# 2__FPGA.net
KiCad netlist of a schematic drawn in Altium Designer
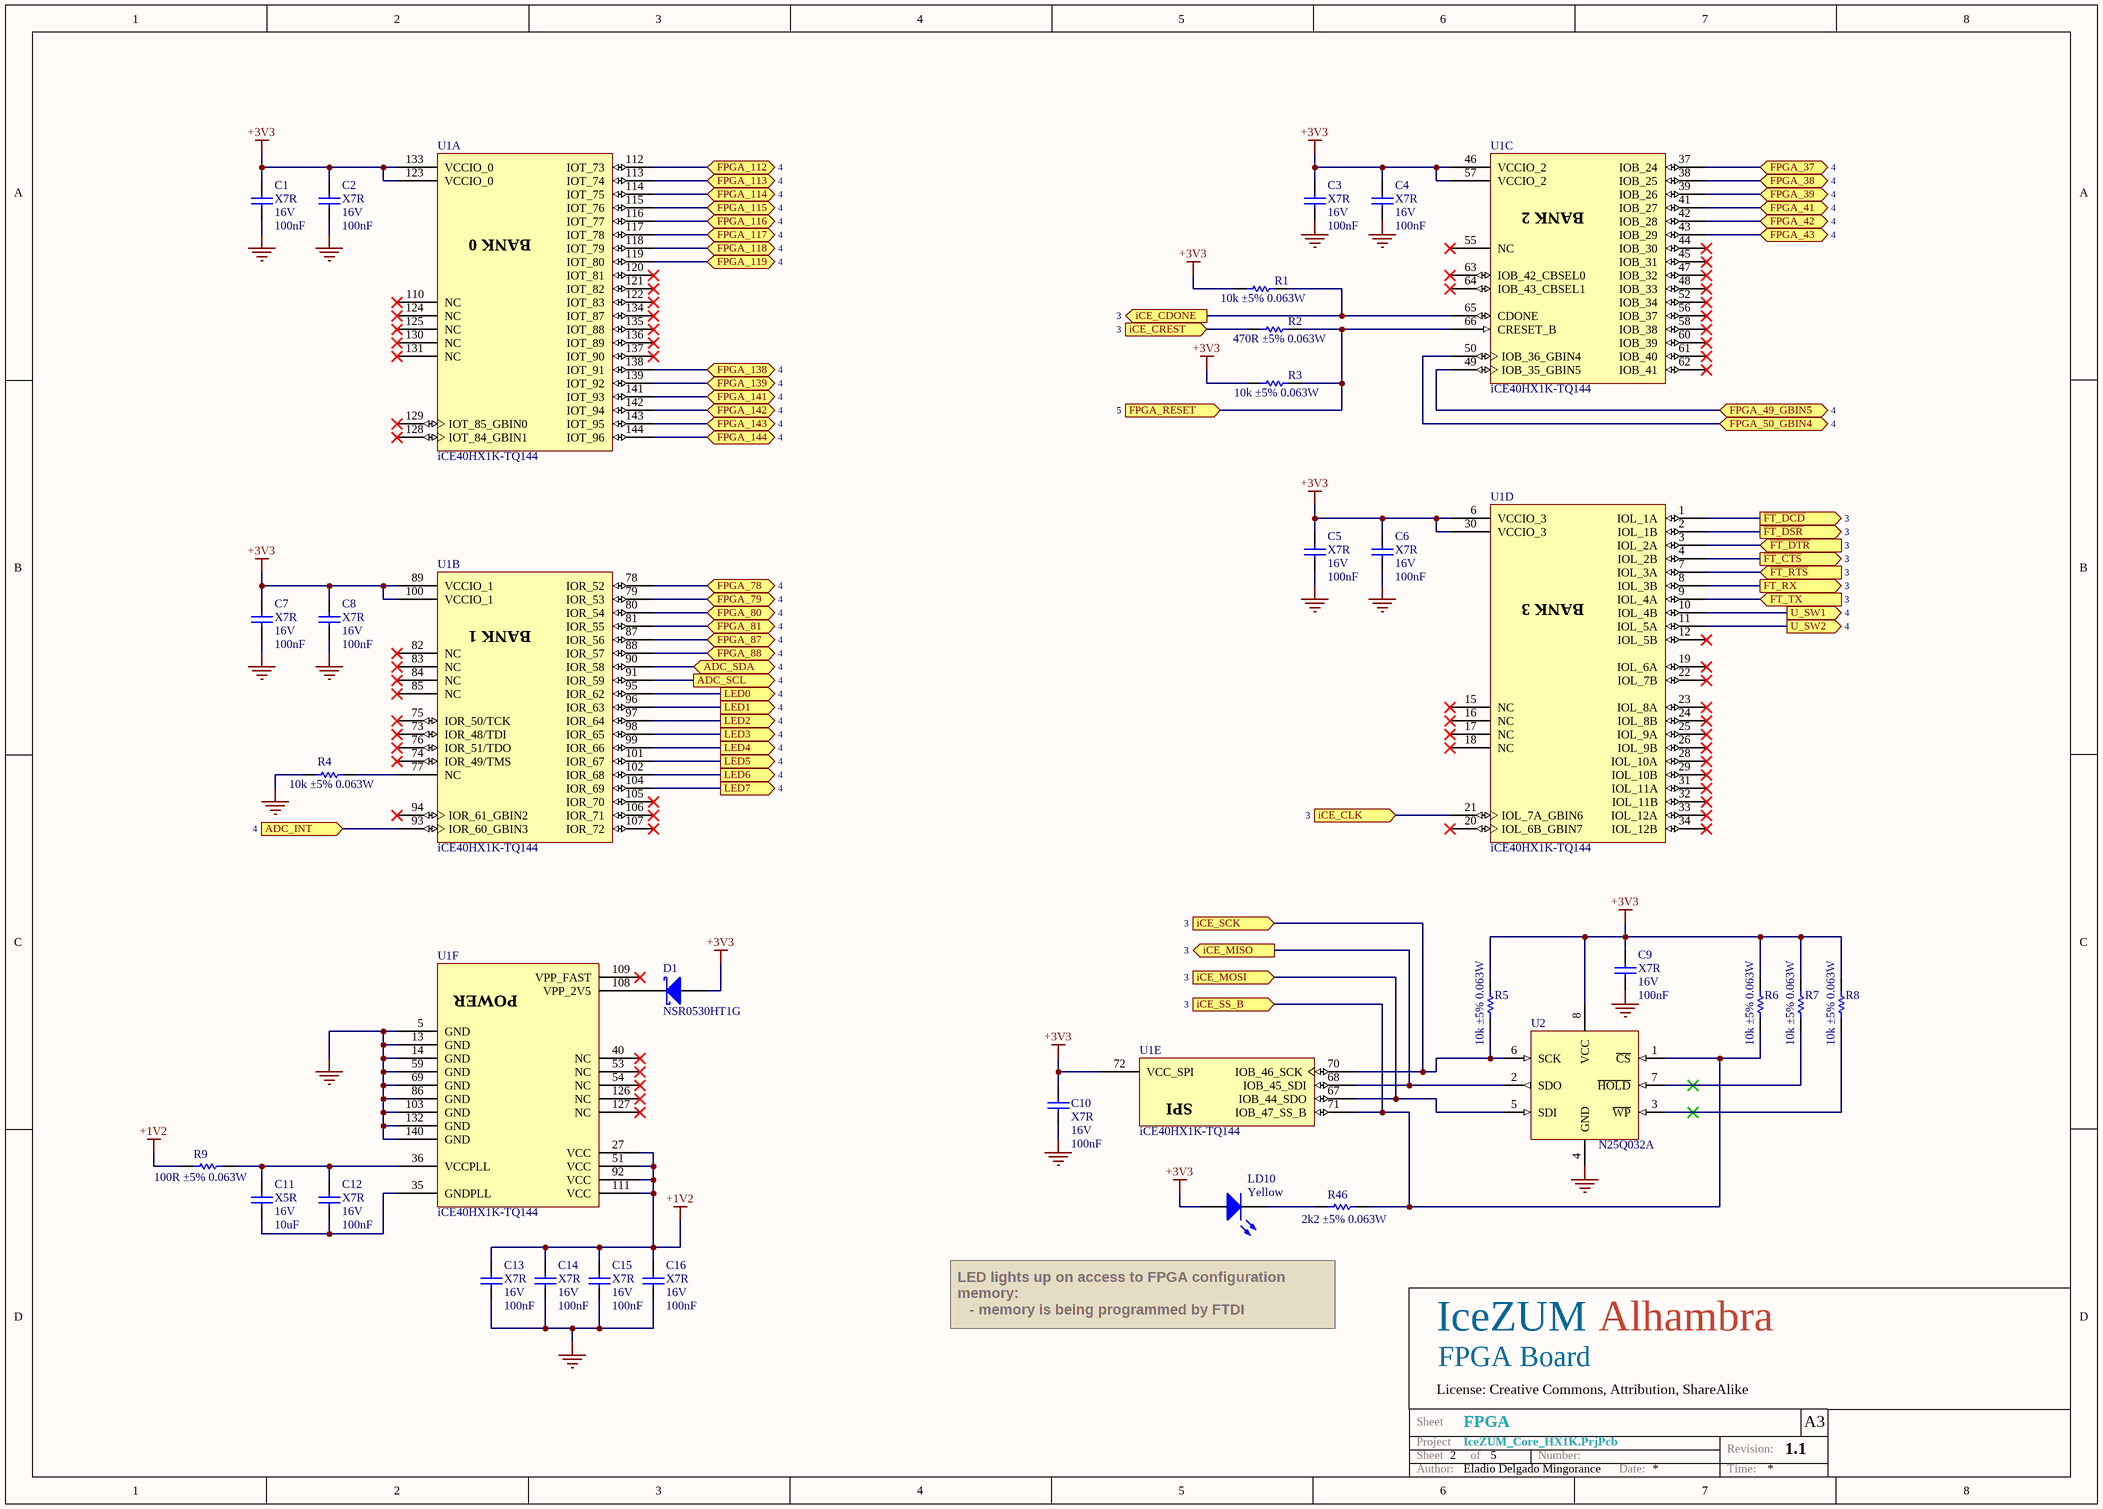
[diagram p0: [2]_FPGA.SchDoc]

(export (version "E")
  (design (tool "Eeschema 10.0.6"))
  (components
    (comp (ref "C1")
      (value "Capacitor")
      (footprint "C0402:C0402")
      (description "Capacitor SMD")
      (fields
        (field (name "DIELECTRIC") "X7R")
        (field (name "VOLTAGE") "16V")
        (field (name "CAPACITANCE") "100nF")
        (field (name "PART NUMBER") "C0402_100nF_16V_±10%")
        (field (name "TOLERANCE") "±10%")
      )
      (libsource (lib "Pasives_Capacitor_SMD") (part "Capacitor"))
    )
    (comp (ref "C2")
      (value "Capacitor")
      (footprint "C0402:C0402")
      (description "Capacitor SMD")
      (fields
        (field (name "DIELECTRIC") "X7R")
        (field (name "VOLTAGE") "16V")
        (field (name "CAPACITANCE") "100nF")
        (field (name "PART NUMBER") "C0402_100nF_16V_±10%")
        (field (name "TOLERANCE") "±10%")
      )
      (libsource (lib "Pasives_Capacitor_SMD") (part "Capacitor"))
    )
    (comp (ref "C3")
      (value "Capacitor")
      (footprint "C0402")
      (description "Capacitor SMD")
      (fields
        (field (name "DIELECTRIC") "X7R")
        (field (name "VOLTAGE") "16V")
        (field (name "CAPACITANCE") "100nF")
        (field (name "PART NUMBER") "C0402_100nF_16V_±10%")
        (field (name "TOLERANCE") "±10%")
      )
      (libsource (lib "Pasives_Capacitor_SMD") (part "Capacitor"))
    )
    (comp (ref "C4")
      (value "Capacitor")
      (footprint "C0402")
      (description "Capacitor SMD")
      (fields
        (field (name "DIELECTRIC") "X7R")
        (field (name "VOLTAGE") "16V")
        (field (name "CAPACITANCE") "100nF")
        (field (name "PART NUMBER") "C0402_100nF_16V_±10%")
        (field (name "TOLERANCE") "±10%")
      )
      (libsource (lib "Pasives_Capacitor_SMD") (part "Capacitor"))
    )
    (comp (ref "C5")
      (value "Capacitor")
      (footprint "C0402")
      (description "Capacitor SMD")
      (fields
        (field (name "DIELECTRIC") "X7R")
        (field (name "VOLTAGE") "16V")
        (field (name "CAPACITANCE") "100nF")
        (field (name "PART NUMBER") "C0402_100nF_16V_±10%")
        (field (name "TOLERANCE") "±10%")
      )
      (libsource (lib "Pasives_Capacitor_SMD") (part "Capacitor"))
    )
    (comp (ref "C6")
      (value "Capacitor")
      (footprint "C0402")
      (description "Capacitor SMD")
      (fields
        (field (name "DIELECTRIC") "X7R")
        (field (name "VOLTAGE") "16V")
        (field (name "CAPACITANCE") "100nF")
        (field (name "PART NUMBER") "C0402_100nF_16V_±10%")
        (field (name "TOLERANCE") "±10%")
      )
      (libsource (lib "Pasives_Capacitor_SMD") (part "Capacitor"))
    )
    (comp (ref "C7")
      (value "Capacitor")
      (footprint "C0402")
      (description "Capacitor SMD")
      (fields
        (field (name "DIELECTRIC") "X7R")
        (field (name "VOLTAGE") "16V")
        (field (name "CAPACITANCE") "100nF")
        (field (name "PART NUMBER") "C0402_100nF_16V_±10%")
        (field (name "TOLERANCE") "±10%")
      )
      (libsource (lib "Pasives_Capacitor_SMD") (part "Capacitor"))
    )
    (comp (ref "C8")
      (value "Capacitor")
      (footprint "C0402")
      (description "Capacitor SMD")
      (fields
        (field (name "DIELECTRIC") "X7R")
        (field (name "VOLTAGE") "16V")
        (field (name "CAPACITANCE") "100nF")
        (field (name "PART NUMBER") "C0402_100nF_16V_±10%")
        (field (name "TOLERANCE") "±10%")
      )
      (libsource (lib "Pasives_Capacitor_SMD") (part "Capacitor"))
    )
    (comp (ref "C9")
      (value "Capacitor")
      (footprint "C0402")
      (description "Capacitor SMD")
      (fields
        (field (name "DIELECTRIC") "X7R")
        (field (name "VOLTAGE") "16V")
        (field (name "CAPACITANCE") "100nF")
        (field (name "PART NUMBER") "C0402_100nF_16V_±10%")
        (field (name "TOLERANCE") "±10%")
      )
      (libsource (lib "Pasives_Capacitor_SMD") (part "Capacitor"))
    )
    (comp (ref "C10")
      (value "Capacitor")
      (footprint "C0402")
      (description "Capacitor SMD")
      (fields
        (field (name "DIELECTRIC") "X7R")
        (field (name "VOLTAGE") "16V")
        (field (name "CAPACITANCE") "100nF")
        (field (name "PART NUMBER") "C0402_100nF_16V_±10%")
        (field (name "TOLERANCE") "±10%")
      )
      (libsource (lib "Pasives_Capacitor_SMD") (part "Capacitor"))
    )
    (comp (ref "C11")
      (value "Capacitor")
      (footprint "C0603")
      (description "Capacitor SMD")
      (fields
        (field (name "DIELECTRIC") "X5R")
        (field (name "VOLTAGE") "16V")
        (field (name "CAPACITANCE") "10uF")
        (field (name "PART NUMBER") "C0603_10uF_16V_±20%")
        (field (name "TOLERANCE") "±20%")
      )
      (libsource (lib "Pasives_Capacitor_SMD") (part "Capacitor"))
    )
    (comp (ref "C12")
      (value "Capacitor")
      (footprint "C0402")
      (description "Capacitor SMD")
      (fields
        (field (name "DIELECTRIC") "X7R")
        (field (name "VOLTAGE") "16V")
        (field (name "CAPACITANCE") "100nF")
        (field (name "PART NUMBER") "C0402_100nF_16V_±10%")
        (field (name "TOLERANCE") "±10%")
      )
      (libsource (lib "Pasives_Capacitor_SMD") (part "Capacitor"))
    )
    (comp (ref "C13")
      (value "Capacitor")
      (footprint "C0402")
      (description "Capacitor SMD")
      (fields
        (field (name "DIELECTRIC") "X7R")
        (field (name "VOLTAGE") "16V")
        (field (name "CAPACITANCE") "100nF")
        (field (name "PART NUMBER") "C0402_100nF_16V_±10%")
        (field (name "TOLERANCE") "±10%")
      )
      (libsource (lib "Pasives_Capacitor_SMD") (part "Capacitor"))
    )
    (comp (ref "C14")
      (value "Capacitor")
      (footprint "C0402")
      (description "Capacitor SMD")
      (fields
        (field (name "DIELECTRIC") "X7R")
        (field (name "VOLTAGE") "16V")
        (field (name "CAPACITANCE") "100nF")
        (field (name "PART NUMBER") "C0402_100nF_16V_±10%")
        (field (name "TOLERANCE") "±10%")
      )
      (libsource (lib "Pasives_Capacitor_SMD") (part "Capacitor"))
    )
    (comp (ref "C15")
      (value "Capacitor")
      (footprint "C0402")
      (description "Capacitor SMD")
      (fields
        (field (name "DIELECTRIC") "X7R")
        (field (name "VOLTAGE") "16V")
        (field (name "CAPACITANCE") "100nF")
        (field (name "PART NUMBER") "C0402_100nF_16V_±10%")
        (field (name "TOLERANCE") "±10%")
      )
      (libsource (lib "Pasives_Capacitor_SMD") (part "Capacitor"))
    )
    (comp (ref "C16")
      (value "Capacitor")
      (footprint "C0402")
      (description "Capacitor SMD")
      (fields
        (field (name "DIELECTRIC") "X7R")
        (field (name "VOLTAGE") "16V")
        (field (name "CAPACITANCE") "100nF")
        (field (name "PART NUMBER") "C0402_100nF_16V_±10%")
        (field (name "TOLERANCE") "±10%")
      )
      (libsource (lib "Pasives_Capacitor_SMD") (part "Capacitor"))
    )
    (comp (ref "D1")
      (value "NSR0530HT1G")
      (footprint "SOD323")
      (description "Schottky Diode")
      (fields (field (name "MANUFACTURER") "On Semiconductor"))
      (libsource (lib "Diodes") (part "Schottky"))
    )
    (comp (ref "LD10")
      (value "Yellow")
      (footprint "LED0603")
      (description "LED")
      (fields (field (name "PART NUMBER") "LED Yellow 0603") (field (name "MANUFACTURER") "KINGBRIGHT"))
      (libsource (lib "Optoelectronics") (part "LED"))
    )
    (comp (ref "R1")
      (value "10k ±5% 0.063W")
      (footprint "R0402")
      (description "Resistor, SMD")
      (fields (field (name "TOLERANCE") "±5%") (field (name "POWER") "0.063W"))
      (libsource (lib "Pasives_Resistor_SMD") (part "Resistor"))
    )
    (comp (ref "R2")
      (value "470R ±5% 0.063W")
      (footprint "R0402")
      (description "Resistor, SMD")
      (fields (field (name "TOLERANCE") "±5%") (field (name "POWER") "0.063W"))
      (libsource (lib "Pasives_Resistor_SMD") (part "Resistor"))
    )
    (comp (ref "R3")
      (value "10k ±5% 0.063W")
      (footprint "R0402")
      (description "Resistor, SMD")
      (fields (field (name "TOLERANCE") "±5%") (field (name "POWER") "0.063W"))
      (libsource (lib "Pasives_Resistor_SMD") (part "Resistor"))
    )
    (comp (ref "R4")
      (value "10k ±5% 0.063W")
      (footprint "R0402")
      (description "Resistor, SMD")
      (fields (field (name "TOLERANCE") "±5%") (field (name "POWER") "0.063W"))
      (libsource (lib "Pasives_Resistor_SMD") (part "Resistor"))
    )
    (comp (ref "R5")
      (value "10k ±5% 0.063W")
      (footprint "R0402")
      (description "Resistor, SMD")
      (fields (field (name "TOLERANCE") "±5%") (field (name "POWER") "0.063W"))
      (libsource (lib "Pasives_Resistor_SMD") (part "Resistor"))
    )
    (comp (ref "R6")
      (value "10k ±5% 0.063W")
      (footprint "R0402")
      (description "Resistor, SMD")
      (fields (field (name "TOLERANCE") "±5%") (field (name "POWER") "0.063W"))
      (libsource (lib "Pasives_Resistor_SMD") (part "Resistor"))
    )
    (comp (ref "R7")
      (value "10k ±5% 0.063W")
      (footprint "R0402")
      (description "Resistor, SMD")
      (fields (field (name "TOLERANCE") "±5%") (field (name "POWER") "0.063W"))
      (libsource (lib "Pasives_Resistor_SMD") (part "Resistor"))
    )
    (comp (ref "R8")
      (value "10k ±5% 0.063W")
      (footprint "R0402")
      (description "Resistor, SMD")
      (fields (field (name "TOLERANCE") "±5%") (field (name "POWER") "0.063W"))
      (libsource (lib "Pasives_Resistor_SMD") (part "Resistor"))
    )
    (comp (ref "R9")
      (value "100R ±5% 0.063W")
      (footprint "R0402")
      (description "Resistor, SMD")
      (fields (field (name "TOLERANCE") "±5%") (field (name "POWER") "0.063W"))
      (libsource (lib "Pasives_Resistor_SMD") (part "Resistor"))
    )
    (comp (ref "R46")
      (value "2k2 ±5% 0.063W")
      (footprint "R0402")
      (description "Resistor, SMD")
      (fields (field (name "TOLERANCE") "±5%") (field (name "POWER") "0.063W"))
      (libsource (lib "Pasives_Resistor_SMD") (part "Resistor"))
    )
    (comp (ref "U1")
      (value "iCE40HX1K-TQ144")
      (footprint "TQFP-144_IPC-MD_HX1K")
      (fields (field (name "PART NUMBER") "iCE40-HX1K") (field (name "MANUFACTURER") "Lattice"))
      (libsource (lib "FPGA") (part "iCE40HX1K-TQ144"))
    )
    (comp (ref "U2")
      (value "N25Q032A")
      (footprint "DFN-8 6x5mm")
      (description "NOR Flash Memory, serial")
      (fields (field (name "MANUFACTURER") "Micron"))
      (libsource (lib "Memory_Serial") (part "N25Q032A"))
    )
  )
  (nets
    (net (code "1") (name "+1V2") (class "Default")
      (node (ref "C13") (pin "2") (pinfunction "2_2") (pintype "passive"))
      (node (ref "C14") (pin "2") (pinfunction "2_2") (pintype "passive"))
      (node (ref "C15") (pin "2") (pinfunction "2_2") (pintype "passive"))
      (node (ref "C16") (pin "2") (pinfunction "2_2") (pintype "passive"))
      (node (ref "R9") (pin "2") (pinfunction "2_2") (pintype "passive"))
      (node (ref "U1") (pin "111") (pinfunction "VCC_111") (pintype "power_in"))
      (node (ref "U1") (pin "27") (pinfunction "VCC_27") (pintype "power_in"))
      (node (ref "U1") (pin "51") (pinfunction "VCC_51") (pintype "power_in"))
      (node (ref "U1") (pin "92") (pinfunction "VCC_92") (pintype "power_in"))
    )
    (net (code "2") (name "+3V3") (class "Default")
      (node (ref "C1") (pin "2") (pinfunction "2_2") (pintype "passive"))
      (node (ref "C10") (pin "2") (pinfunction "2_2") (pintype "passive"))
      (node (ref "C2") (pin "2") (pinfunction "2_2") (pintype "passive"))
      (node (ref "C3") (pin "2") (pinfunction "2_2") (pintype "passive"))
      (node (ref "C4") (pin "2") (pinfunction "2_2") (pintype "passive"))
      (node (ref "C5") (pin "2") (pinfunction "2_2") (pintype "passive"))
      (node (ref "C6") (pin "2") (pinfunction "2_2") (pintype "passive"))
      (node (ref "C7") (pin "2") (pinfunction "2_2") (pintype "passive"))
      (node (ref "C8") (pin "2") (pinfunction "2_2") (pintype "passive"))
      (node (ref "C9") (pin "1") (pinfunction "1_1") (pintype "passive"))
      (node (ref "D1") (pin "A") (pinfunction "A_A") (pintype "passive"))
      (node (ref "LD10") (pin "A") (pinfunction "A_A") (pintype "passive"))
      (node (ref "R1") (pin "1") (pinfunction "1_1") (pintype "passive"))
      (node (ref "R3") (pin "1") (pinfunction "1_1") (pintype "passive"))
      (node (ref "R5") (pin "2") (pinfunction "2_2") (pintype "passive"))
      (node (ref "R6") (pin "2") (pinfunction "2_2") (pintype "passive"))
      (node (ref "R7") (pin "2") (pinfunction "2_2") (pintype "passive"))
      (node (ref "R8") (pin "2") (pinfunction "2_2") (pintype "passive"))
      (node (ref "U1") (pin "100") (pinfunction "VCCIO_1_100") (pintype "power_in"))
      (node (ref "U1") (pin "123") (pinfunction "VCCIO_0_123") (pintype "power_in"))
      (node (ref "U1") (pin "133") (pinfunction "VCCIO_0_133") (pintype "power_in"))
      (node (ref "U1") (pin "30") (pinfunction "VCCIO_3_30") (pintype "power_in"))
      (node (ref "U1") (pin "46") (pinfunction "VCCIO_2_46") (pintype "power_in"))
      (node (ref "U1") (pin "57") (pinfunction "VCCIO_2_57") (pintype "power_in"))
      (node (ref "U1") (pin "6") (pinfunction "VCCIO_3_6") (pintype "power_in"))
      (node (ref "U1") (pin "72") (pinfunction "VCC_SPI_72") (pintype "power_in"))
      (node (ref "U1") (pin "89") (pinfunction "VCCIO_1_89") (pintype "power_in"))
      (node (ref "U2") (pin "8") (pinfunction "VCC_8") (pintype "power_in"))
    )
    (net (code "3") (name "/ADC_INT") (class "Default")
      (node (ref "U1") (pin "93") (pinfunction "IOR_60_GBIN3_93") (pintype "bidirectional"))
    )
    (net (code "4") (name "/ADC_SCL") (class "Default")
      (node (ref "U1") (pin "91") (pinfunction "IOR_59_91") (pintype "bidirectional"))
    )
    (net (code "5") (name "/ADC_SDA") (class "Default")
      (node (ref "U1") (pin "90") (pinfunction "IOR_58_90") (pintype "bidirectional"))
    )
    (net (code "6") (name "/FPGA_37") (class "Default")
      (node (ref "U1") (pin "37") (pinfunction "IOB_24_37") (pintype "bidirectional"))
    )
    (net (code "7") (name "/FPGA_38") (class "Default")
      (node (ref "U1") (pin "38") (pinfunction "IOB_25_38") (pintype "bidirectional"))
    )
    (net (code "8") (name "/FPGA_39") (class "Default")
      (node (ref "U1") (pin "39") (pinfunction "IOB_26_39") (pintype "bidirectional"))
    )
    (net (code "9") (name "/FPGA_41") (class "Default")
      (node (ref "U1") (pin "41") (pinfunction "IOB_27_41") (pintype "bidirectional"))
    )
    (net (code "10") (name "/FPGA_42") (class "Default")
      (node (ref "U1") (pin "42") (pinfunction "IOB_28_42") (pintype "bidirectional"))
    )
    (net (code "11") (name "/FPGA_43") (class "Default")
      (node (ref "U1") (pin "43") (pinfunction "IOB_29_43") (pintype "bidirectional"))
    )
    (net (code "12") (name "/FPGA_49_GBIN5") (class "Default")
      (node (ref "U1") (pin "49") (pinfunction "IOB_35_GBIN5_49") (pintype "bidirectional"))
    )
    (net (code "13") (name "/FPGA_50_GBIN4") (class "Default")
      (node (ref "U1") (pin "50") (pinfunction "IOB_36_GBIN4_50") (pintype "bidirectional"))
    )
    (net (code "14") (name "/FPGA_78") (class "Default")
      (node (ref "U1") (pin "78") (pinfunction "IOR_52_78") (pintype "bidirectional"))
    )
    (net (code "15") (name "/FPGA_79") (class "Default")
      (node (ref "U1") (pin "79") (pinfunction "IOR_53_79") (pintype "bidirectional"))
    )
    (net (code "16") (name "/FPGA_80") (class "Default")
      (node (ref "U1") (pin "80") (pinfunction "IOR_54_80") (pintype "bidirectional"))
    )
    (net (code "17") (name "/FPGA_81") (class "Default")
      (node (ref "U1") (pin "81") (pinfunction "IOR_55_81") (pintype "bidirectional"))
    )
    (net (code "18") (name "/FPGA_87") (class "Default")
      (node (ref "U1") (pin "87") (pinfunction "IOR_56_87") (pintype "bidirectional"))
    )
    (net (code "19") (name "/FPGA_88") (class "Default")
      (node (ref "U1") (pin "88") (pinfunction "IOR_57_88") (pintype "bidirectional"))
    )
    (net (code "20") (name "/FPGA_112") (class "Default")
      (node (ref "U1") (pin "112") (pinfunction "IOT_73_112") (pintype "bidirectional"))
    )
    (net (code "21") (name "/FPGA_113") (class "Default")
      (node (ref "U1") (pin "113") (pinfunction "IOT_74_113") (pintype "bidirectional"))
    )
    (net (code "22") (name "/FPGA_114") (class "Default")
      (node (ref "U1") (pin "114") (pinfunction "IOT_75_114") (pintype "bidirectional"))
    )
    (net (code "23") (name "/FPGA_115") (class "Default")
      (node (ref "U1") (pin "115") (pinfunction "IOT_76_115") (pintype "bidirectional"))
    )
    (net (code "24") (name "/FPGA_116") (class "Default")
      (node (ref "U1") (pin "116") (pinfunction "IOT_77_116") (pintype "bidirectional"))
    )
    (net (code "25") (name "/FPGA_117") (class "Default")
      (node (ref "U1") (pin "117") (pinfunction "IOT_78_117") (pintype "bidirectional"))
    )
    (net (code "26") (name "/FPGA_118") (class "Default")
      (node (ref "U1") (pin "118") (pinfunction "IOT_79_118") (pintype "bidirectional"))
    )
    (net (code "27") (name "/FPGA_119") (class "Default")
      (node (ref "U1") (pin "119") (pinfunction "IOT_80_119") (pintype "bidirectional"))
    )
    (net (code "28") (name "/FPGA_138") (class "Default")
      (node (ref "U1") (pin "138") (pinfunction "IOT_91_138") (pintype "bidirectional"))
    )
    (net (code "29") (name "/FPGA_139") (class "Default")
      (node (ref "U1") (pin "139") (pinfunction "IOT_92_139") (pintype "bidirectional"))
    )
    (net (code "30") (name "/FPGA_141") (class "Default")
      (node (ref "U1") (pin "141") (pinfunction "IOT_93_141") (pintype "bidirectional"))
    )
    (net (code "31") (name "/FPGA_142") (class "Default")
      (node (ref "U1") (pin "142") (pinfunction "IOT_94_142") (pintype "bidirectional"))
    )
    (net (code "32") (name "/FPGA_143") (class "Default")
      (node (ref "U1") (pin "143") (pinfunction "IOT_95_143") (pintype "bidirectional"))
    )
    (net (code "33") (name "/FPGA_144") (class "Default")
      (node (ref "U1") (pin "144") (pinfunction "IOT_96_144") (pintype "bidirectional"))
    )
    (net (code "34") (name "/FPGA_RESET") (class "Default")
      (node (ref "R2") (pin "2") (pinfunction "2_2") (pintype "passive"))
      (node (ref "R3") (pin "2") (pinfunction "2_2") (pintype "passive"))
      (node (ref "U1") (pin "66") (pinfunction "CRESET_B_66") (pintype "input"))
    )
    (net (code "35") (name "/FT_CTS") (class "Default")
      (node (ref "U1") (pin "4") (pinfunction "IOL_2B_4") (pintype "bidirectional"))
    )
    (net (code "36") (name "/FT_DCD") (class "Default")
      (node (ref "U1") (pin "1") (pinfunction "IOL_1A_1") (pintype "bidirectional"))
    )
    (net (code "37") (name "/FT_DSR") (class "Default")
      (node (ref "U1") (pin "2") (pinfunction "IOL_1B_2") (pintype "bidirectional"))
    )
    (net (code "38") (name "/FT_DTR") (class "Default")
      (node (ref "U1") (pin "3") (pinfunction "IOL_2A_3") (pintype "bidirectional"))
    )
    (net (code "39") (name "/FT_RTS") (class "Default")
      (node (ref "U1") (pin "7") (pinfunction "IOL_3A_7") (pintype "bidirectional"))
    )
    (net (code "40") (name "/FT_RX") (class "Default")
      (node (ref "U1") (pin "8") (pinfunction "IOL_3B_8") (pintype "bidirectional"))
    )
    (net (code "41") (name "/FT_TX") (class "Default")
      (node (ref "U1") (pin "9") (pinfunction "IOL_4A_9") (pintype "bidirectional"))
    )
    (net (code "42") (name "/LED0") (class "Default")
      (node (ref "U1") (pin "95") (pinfunction "IOR_62_95") (pintype "bidirectional"))
    )
    (net (code "43") (name "/LED1") (class "Default")
      (node (ref "U1") (pin "96") (pinfunction "IOR_63_96") (pintype "bidirectional"))
    )
    (net (code "44") (name "/LED2") (class "Default")
      (node (ref "U1") (pin "97") (pinfunction "IOR_64_97") (pintype "bidirectional"))
    )
    (net (code "45") (name "/LED3") (class "Default")
      (node (ref "U1") (pin "98") (pinfunction "IOR_65_98") (pintype "bidirectional"))
    )
    (net (code "46") (name "/LED4") (class "Default")
      (node (ref "U1") (pin "99") (pinfunction "IOR_66_99") (pintype "bidirectional"))
    )
    (net (code "47") (name "/LED5") (class "Default")
      (node (ref "U1") (pin "101") (pinfunction "IOR_67_101") (pintype "bidirectional"))
    )
    (net (code "48") (name "/LED6") (class "Default")
      (node (ref "U1") (pin "102") (pinfunction "IOR_68_102") (pintype "bidirectional"))
    )
    (net (code "49") (name "/LED7") (class "Default")
      (node (ref "U1") (pin "104") (pinfunction "IOR_69_104") (pintype "bidirectional"))
    )
    (net (code "50") (name "/U_SW1") (class "Default")
      (node (ref "U1") (pin "10") (pinfunction "IOL_4B_10") (pintype "bidirectional"))
    )
    (net (code "51") (name "/U_SW2") (class "Default")
      (node (ref "U1") (pin "11") (pinfunction "IOL_5A_11") (pintype "bidirectional"))
    )
    (net (code "52") (name "/iCE_CDONE") (class "Default")
      (node (ref "R1") (pin "2") (pinfunction "2_2") (pintype "passive"))
      (node (ref "U1") (pin "65") (pinfunction "CDONE_65") (pintype "bidirectional"))
    )
    (net (code "53") (name "/iCE_CLK") (class "Default")
      (node (ref "U1") (pin "21") (pinfunction "IOL_7A_GBIN6_21") (pintype "bidirectional"))
    )
    (net (code "54") (name "/iCE_CREST") (class "Default")
      (node (ref "R2") (pin "1") (pinfunction "1_1") (pintype "passive"))
    )
    (net (code "55") (name "/iCE_MISO") (class "Default")
      (node (ref "U1") (pin "68") (pinfunction "IOB_45_SDI_68") (pintype "bidirectional"))
      (node (ref "U2") (pin "2") (pinfunction "SDO_2") (pintype "output"))
    )
    (net (code "56") (name "/iCE_MOSI") (class "Default")
      (node (ref "U1") (pin "67") (pinfunction "IOB_44_SDO_67") (pintype "bidirectional"))
      (node (ref "U2") (pin "5") (pinfunction "SDI_5") (pintype "input"))
    )
    (net (code "57") (name "/iCE_SCK") (class "Default")
      (node (ref "R5") (pin "1") (pinfunction "1_1") (pintype "passive"))
      (node (ref "U1") (pin "70") (pinfunction "IOB_46_SCK_70") (pintype "bidirectional"))
      (node (ref "U2") (pin "6") (pinfunction "SCK_6") (pintype "input"))
    )
    (net (code "58") (name "/iCE_SS_B") (class "Default")
      (node (ref "R46") (pin "2") (pinfunction "2_2") (pintype "passive"))
      (node (ref "R6") (pin "1") (pinfunction "1_1") (pintype "passive"))
      (node (ref "U1") (pin "71") (pinfunction "IOB_47_SS_B_71") (pintype "bidirectional"))
      (node (ref "U2") (pin "1") (pinfunction "CS_1") (pintype "input"))
    )
    (net (code "59") (name "GND") (class "Default")
      (node (ref "C1") (pin "1") (pinfunction "1_1") (pintype "passive"))
      (node (ref "C10") (pin "1") (pinfunction "1_1") (pintype "passive"))
      (node (ref "C13") (pin "1") (pinfunction "1_1") (pintype "passive"))
      (node (ref "C14") (pin "1") (pinfunction "1_1") (pintype "passive"))
      (node (ref "C15") (pin "1") (pinfunction "1_1") (pintype "passive"))
      (node (ref "C16") (pin "1") (pinfunction "1_1") (pintype "passive"))
      (node (ref "C2") (pin "1") (pinfunction "1_1") (pintype "passive"))
      (node (ref "C3") (pin "1") (pinfunction "1_1") (pintype "passive"))
      (node (ref "C4") (pin "1") (pinfunction "1_1") (pintype "passive"))
      (node (ref "C5") (pin "1") (pinfunction "1_1") (pintype "passive"))
      (node (ref "C6") (pin "1") (pinfunction "1_1") (pintype "passive"))
      (node (ref "C7") (pin "1") (pinfunction "1_1") (pintype "passive"))
      (node (ref "C8") (pin "1") (pinfunction "1_1") (pintype "passive"))
      (node (ref "C9") (pin "2") (pinfunction "2_2") (pintype "passive"))
      (node (ref "R4") (pin "1") (pinfunction "1_1") (pintype "passive"))
      (node (ref "U1") (pin "103") (pinfunction "GND_103") (pintype "power_in"))
      (node (ref "U1") (pin "13") (pinfunction "GND_13") (pintype "power_in"))
      (node (ref "U1") (pin "132") (pinfunction "GND_132") (pintype "power_in"))
      (node (ref "U1") (pin "14") (pinfunction "GND_14") (pintype "power_in"))
      (node (ref "U1") (pin "140") (pinfunction "GND_140") (pintype "power_in"))
      (node (ref "U1") (pin "5") (pinfunction "GND_5") (pintype "power_in"))
      (node (ref "U1") (pin "59") (pinfunction "GND_59") (pintype "power_in"))
      (node (ref "U1") (pin "69") (pinfunction "GND_69") (pintype "power_in"))
      (node (ref "U1") (pin "86") (pinfunction "GND_86") (pintype "power_in"))
      (node (ref "U2") (pin "4") (pinfunction "GND_4") (pintype "power_in"))
    )
    (net (code "60") (name "Net-(D1-K)") (class "Default")
      (node (ref "D1") (pin "k") (pinfunction "K_k") (pintype "passive"))
      (node (ref "U1") (pin "108") (pinfunction "VPP_2V5_108") (pintype "power_in"))
    )
    (net (code "61") (name "Net-(LD10-PadK)") (class "Default")
      (node (ref "LD10") (pin "K") (pinfunction "K_K") (pintype "passive"))
      (node (ref "R46") (pin "1") (pinfunction "1_1") (pintype "passive"))
    )
    (net (code "62") (name "Net-(R4-Pad2)") (class "Default")
      (node (ref "R4") (pin "2") (pinfunction "2_2") (pintype "passive"))
      (node (ref "U1") (pin "77") (pinfunction "NC_77") (pintype "passive"))
    )
    (net (code "63") (name "Net-(U1F-GNDPLL)") (class "Default")
      (node (ref "C11") (pin "1") (pinfunction "1_1") (pintype "passive"))
      (node (ref "C12") (pin "1") (pinfunction "1_1") (pintype "passive"))
      (node (ref "U1") (pin "35") (pinfunction "GNDPLL_35") (pintype "power_in"))
    )
    (net (code "64") (name "Net-(U1F-VCCPLL)") (class "Default")
      (node (ref "C11") (pin "2") (pinfunction "2_2") (pintype "passive"))
      (node (ref "C12") (pin "2") (pinfunction "2_2") (pintype "passive"))
      (node (ref "R9") (pin "1") (pinfunction "1_1") (pintype "passive"))
      (node (ref "U1") (pin "36") (pinfunction "VCCPLL_36") (pintype "power_in"))
    )
    (net (code "65") (name "Net-(U2-HOLD)") (class "Default")
      (node (ref "R7") (pin "1") (pinfunction "1_1") (pintype "passive"))
      (node (ref "U2") (pin "7") (pinfunction "HOLD_7") (pintype "input"))
    )
    (net (code "66") (name "Net-(U2-WP)") (class "Default")
      (node (ref "R8") (pin "1") (pinfunction "1_1") (pintype "passive"))
      (node (ref "U2") (pin "3") (pinfunction "WP_3") (pintype "input"))
    )
    (net (code "67") (name "unconnected-(U1A-IOT_81-Pad120)") (class "Default")
      (node (ref "U1") (pin "120") (pinfunction "IOT_81_120") (pintype "bidirectional+no_connect"))
    )
    (net (code "68") (name "unconnected-(U1A-IOT_82-Pad121)") (class "Default")
      (node (ref "U1") (pin "121") (pinfunction "IOT_82_121") (pintype "bidirectional+no_connect"))
    )
    (net (code "69") (name "unconnected-(U1A-IOT_83-Pad122)") (class "Default")
      (node (ref "U1") (pin "122") (pinfunction "IOT_83_122") (pintype "bidirectional+no_connect"))
    )
    (net (code "70") (name "unconnected-(U1A-IOT_84_GBIN1-Pad128)") (class "Default")
      (node (ref "U1") (pin "128") (pinfunction "IOT_84_GBIN1_128") (pintype "bidirectional+no_connect"))
    )
    (net (code "71") (name "unconnected-(U1A-IOT_85_GBIN0-Pad129)") (class "Default")
      (node (ref "U1") (pin "129") (pinfunction "IOT_85_GBIN0_129") (pintype "bidirectional+no_connect"))
    )
    (net (code "72") (name "unconnected-(U1A-IOT_87-Pad134)") (class "Default")
      (node (ref "U1") (pin "134") (pinfunction "IOT_87_134") (pintype "bidirectional+no_connect"))
    )
    (net (code "73") (name "unconnected-(U1A-IOT_88-Pad135)") (class "Default")
      (node (ref "U1") (pin "135") (pinfunction "IOT_88_135") (pintype "bidirectional+no_connect"))
    )
    (net (code "74") (name "unconnected-(U1A-IOT_89-Pad136)") (class "Default")
      (node (ref "U1") (pin "136") (pinfunction "IOT_89_136") (pintype "bidirectional+no_connect"))
    )
    (net (code "75") (name "unconnected-(U1A-IOT_90-Pad137)") (class "Default")
      (node (ref "U1") (pin "137") (pinfunction "IOT_90_137") (pintype "bidirectional+no_connect"))
    )
    (net (code "76") (name "unconnected-(U1A-NC-Pad110)") (class "Default")
      (node (ref "U1") (pin "110") (pinfunction "NC_110") (pintype "passive+no_connect"))
    )
    (net (code "77") (name "unconnected-(U1A-NC-Pad124)") (class "Default")
      (node (ref "U1") (pin "124") (pinfunction "NC_124") (pintype "passive+no_connect"))
    )
    (net (code "78") (name "unconnected-(U1A-NC-Pad125)") (class "Default")
      (node (ref "U1") (pin "125") (pinfunction "NC_125") (pintype "passive+no_connect"))
    )
    (net (code "79") (name "unconnected-(U1A-NC-Pad130)") (class "Default")
      (node (ref "U1") (pin "130") (pinfunction "NC_130") (pintype "passive+no_connect"))
    )
    (net (code "80") (name "unconnected-(U1A-NC-Pad131)") (class "Default")
      (node (ref "U1") (pin "131") (pinfunction "NC_131") (pintype "passive+no_connect"))
    )
    (net (code "81") (name "unconnected-(U1B-IOR_48{slash}TDI-Pad73)") (class "Default")
      (node (ref "U1") (pin "73") (pinfunction "IOR_48/TDI_73") (pintype "bidirectional+no_connect"))
    )
    (net (code "82") (name "unconnected-(U1B-IOR_49{slash}TMS-Pad74)") (class "Default")
      (node (ref "U1") (pin "74") (pinfunction "IOR_49/TMS_74") (pintype "bidirectional+no_connect"))
    )
    (net (code "83") (name "unconnected-(U1B-IOR_50{slash}TCK-Pad75)") (class "Default")
      (node (ref "U1") (pin "75") (pinfunction "IOR_50/TCK_75") (pintype "bidirectional+no_connect"))
    )
    (net (code "84") (name "unconnected-(U1B-IOR_51{slash}TDO-Pad76)") (class "Default")
      (node (ref "U1") (pin "76") (pinfunction "IOR_51/TDO_76") (pintype "bidirectional+no_connect"))
    )
    (net (code "85") (name "unconnected-(U1B-IOR_61_GBIN2-Pad94)") (class "Default")
      (node (ref "U1") (pin "94") (pinfunction "IOR_61_GBIN2_94") (pintype "bidirectional+no_connect"))
    )
    (net (code "86") (name "unconnected-(U1B-IOR_70-Pad105)") (class "Default")
      (node (ref "U1") (pin "105") (pinfunction "IOR_70_105") (pintype "bidirectional+no_connect"))
    )
    (net (code "87") (name "unconnected-(U1B-IOR_71-Pad106)") (class "Default")
      (node (ref "U1") (pin "106") (pinfunction "IOR_71_106") (pintype "bidirectional+no_connect"))
    )
    (net (code "88") (name "unconnected-(U1B-IOR_72-Pad107)") (class "Default")
      (node (ref "U1") (pin "107") (pinfunction "IOR_72_107") (pintype "bidirectional+no_connect"))
    )
    (net (code "89") (name "unconnected-(U1B-NC-Pad82)") (class "Default")
      (node (ref "U1") (pin "82") (pinfunction "NC_82") (pintype "passive+no_connect"))
    )
    (net (code "90") (name "unconnected-(U1B-NC-Pad83)") (class "Default")
      (node (ref "U1") (pin "83") (pinfunction "NC_83") (pintype "passive+no_connect"))
    )
    (net (code "91") (name "unconnected-(U1B-NC-Pad84)") (class "Default")
      (node (ref "U1") (pin "84") (pinfunction "NC_84") (pintype "passive+no_connect"))
    )
    (net (code "92") (name "unconnected-(U1B-NC-Pad85)") (class "Default")
      (node (ref "U1") (pin "85") (pinfunction "NC_85") (pintype "passive+no_connect"))
    )
    (net (code "93") (name "unconnected-(U1C-IOB_30-Pad44)") (class "Default")
      (node (ref "U1") (pin "44") (pinfunction "IOB_30_44") (pintype "bidirectional+no_connect"))
    )
    (net (code "94") (name "unconnected-(U1C-IOB_31-Pad45)") (class "Default")
      (node (ref "U1") (pin "45") (pinfunction "IOB_31_45") (pintype "bidirectional+no_connect"))
    )
    (net (code "95") (name "unconnected-(U1C-IOB_32-Pad47)") (class "Default")
      (node (ref "U1") (pin "47") (pinfunction "IOB_32_47") (pintype "bidirectional+no_connect"))
    )
    (net (code "96") (name "unconnected-(U1C-IOB_33-Pad48)") (class "Default")
      (node (ref "U1") (pin "48") (pinfunction "IOB_33_48") (pintype "bidirectional+no_connect"))
    )
    (net (code "97") (name "unconnected-(U1C-IOB_34-Pad52)") (class "Default")
      (node (ref "U1") (pin "52") (pinfunction "IOB_34_52") (pintype "bidirectional+no_connect"))
    )
    (net (code "98") (name "unconnected-(U1C-IOB_37-Pad56)") (class "Default")
      (node (ref "U1") (pin "56") (pinfunction "IOB_37_56") (pintype "bidirectional+no_connect"))
    )
    (net (code "99") (name "unconnected-(U1C-IOB_38-Pad58)") (class "Default")
      (node (ref "U1") (pin "58") (pinfunction "IOB_38_58") (pintype "bidirectional+no_connect"))
    )
    (net (code "100") (name "unconnected-(U1C-IOB_39-Pad60)") (class "Default")
      (node (ref "U1") (pin "60") (pinfunction "IOB_39_60") (pintype "bidirectional+no_connect"))
    )
    (net (code "101") (name "unconnected-(U1C-IOB_40-Pad61)") (class "Default")
      (node (ref "U1") (pin "61") (pinfunction "IOB_40_61") (pintype "bidirectional+no_connect"))
    )
    (net (code "102") (name "unconnected-(U1C-IOB_41-Pad62)") (class "Default")
      (node (ref "U1") (pin "62") (pinfunction "IOB_41_62") (pintype "bidirectional+no_connect"))
    )
    (net (code "103") (name "unconnected-(U1C-IOB_42_CBSEL0-Pad63)") (class "Default")
      (node (ref "U1") (pin "63") (pinfunction "IOB_42_CBSEL0_63") (pintype "bidirectional+no_connect"))
    )
    (net (code "104") (name "unconnected-(U1C-IOB_43_CBSEL1-Pad64)") (class "Default")
      (node (ref "U1") (pin "64") (pinfunction "IOB_43_CBSEL1_64") (pintype "bidirectional+no_connect"))
    )
    (net (code "105") (name "unconnected-(U1C-NC-Pad55)") (class "Default")
      (node (ref "U1") (pin "55") (pinfunction "NC_55") (pintype "passive+no_connect"))
    )
    (net (code "106") (name "unconnected-(U1D-IOL_5B-Pad12)") (class "Default")
      (node (ref "U1") (pin "12") (pinfunction "IOL_5B_12") (pintype "bidirectional+no_connect"))
    )
    (net (code "107") (name "unconnected-(U1D-IOL_6A-Pad19)") (class "Default")
      (node (ref "U1") (pin "19") (pinfunction "IOL_6A_19") (pintype "bidirectional+no_connect"))
    )
    (net (code "108") (name "unconnected-(U1D-IOL_6B_GBIN7-Pad20)") (class "Default")
      (node (ref "U1") (pin "20") (pinfunction "IOL_6B_GBIN7_20") (pintype "bidirectional+no_connect"))
    )
    (net (code "109") (name "unconnected-(U1D-IOL_7B-Pad22)") (class "Default")
      (node (ref "U1") (pin "22") (pinfunction "IOL_7B_22") (pintype "bidirectional+no_connect"))
    )
    (net (code "110") (name "unconnected-(U1D-IOL_8A-Pad23)") (class "Default")
      (node (ref "U1") (pin "23") (pinfunction "IOL_8A_23") (pintype "bidirectional+no_connect"))
    )
    (net (code "111") (name "unconnected-(U1D-IOL_8B-Pad24)") (class "Default")
      (node (ref "U1") (pin "24") (pinfunction "IOL_8B_24") (pintype "bidirectional+no_connect"))
    )
    (net (code "112") (name "unconnected-(U1D-IOL_9A-Pad25)") (class "Default")
      (node (ref "U1") (pin "25") (pinfunction "IOL_9A_25") (pintype "bidirectional+no_connect"))
    )
    (net (code "113") (name "unconnected-(U1D-IOL_9B-Pad26)") (class "Default")
      (node (ref "U1") (pin "26") (pinfunction "IOL_9B_26") (pintype "bidirectional+no_connect"))
    )
    (net (code "114") (name "unconnected-(U1D-IOL_10A-Pad28)") (class "Default")
      (node (ref "U1") (pin "28") (pinfunction "IOL_10A_28") (pintype "bidirectional+no_connect"))
    )
    (net (code "115") (name "unconnected-(U1D-IOL_10B-Pad29)") (class "Default")
      (node (ref "U1") (pin "29") (pinfunction "IOL_10B_29") (pintype "bidirectional+no_connect"))
    )
    (net (code "116") (name "unconnected-(U1D-IOL_11A-Pad31)") (class "Default")
      (node (ref "U1") (pin "31") (pinfunction "IOL_11A_31") (pintype "bidirectional+no_connect"))
    )
    (net (code "117") (name "unconnected-(U1D-IOL_11B-Pad32)") (class "Default")
      (node (ref "U1") (pin "32") (pinfunction "IOL_11B_32") (pintype "bidirectional+no_connect"))
    )
    (net (code "118") (name "unconnected-(U1D-IOL_12A-Pad33)") (class "Default")
      (node (ref "U1") (pin "33") (pinfunction "IOL_12A_33") (pintype "bidirectional+no_connect"))
    )
    (net (code "119") (name "unconnected-(U1D-IOL_12B-Pad34)") (class "Default")
      (node (ref "U1") (pin "34") (pinfunction "IOL_12B_34") (pintype "bidirectional+no_connect"))
    )
    (net (code "120") (name "unconnected-(U1D-NC-Pad15)") (class "Default")
      (node (ref "U1") (pin "15") (pinfunction "NC_15") (pintype "passive+no_connect"))
    )
    (net (code "121") (name "unconnected-(U1D-NC-Pad16)") (class "Default")
      (node (ref "U1") (pin "16") (pinfunction "NC_16") (pintype "passive+no_connect"))
    )
    (net (code "122") (name "unconnected-(U1D-NC-Pad17)") (class "Default")
      (node (ref "U1") (pin "17") (pinfunction "NC_17") (pintype "passive+no_connect"))
    )
    (net (code "123") (name "unconnected-(U1D-NC-Pad18)") (class "Default")
      (node (ref "U1") (pin "18") (pinfunction "NC_18") (pintype "passive+no_connect"))
    )
    (net (code "124") (name "unconnected-(U1F-NC-Pad40)") (class "Default")
      (node (ref "U1") (pin "40") (pinfunction "NC_40") (pintype "passive+no_connect"))
    )
    (net (code "125") (name "unconnected-(U1F-NC-Pad53)") (class "Default")
      (node (ref "U1") (pin "53") (pinfunction "NC_53") (pintype "passive+no_connect"))
    )
    (net (code "126") (name "unconnected-(U1F-NC-Pad54)") (class "Default")
      (node (ref "U1") (pin "54") (pinfunction "NC_54") (pintype "passive+no_connect"))
    )
    (net (code "127") (name "unconnected-(U1F-NC-Pad126)") (class "Default")
      (node (ref "U1") (pin "126") (pinfunction "NC_126") (pintype "passive+no_connect"))
    )
    (net (code "128") (name "unconnected-(U1F-NC-Pad127)") (class "Default")
      (node (ref "U1") (pin "127") (pinfunction "NC_127") (pintype "passive+no_connect"))
    )
    (net (code "129") (name "unconnected-(U1F-VPP_FAST-Pad109)") (class "Default")
      (node (ref "U1") (pin "109") (pinfunction "VPP_FAST_109") (pintype "power_in+no_connect"))
    )
  )
)
